# FPGA-3.net
KiCad netlist of a schematic drawn in Altium Designer
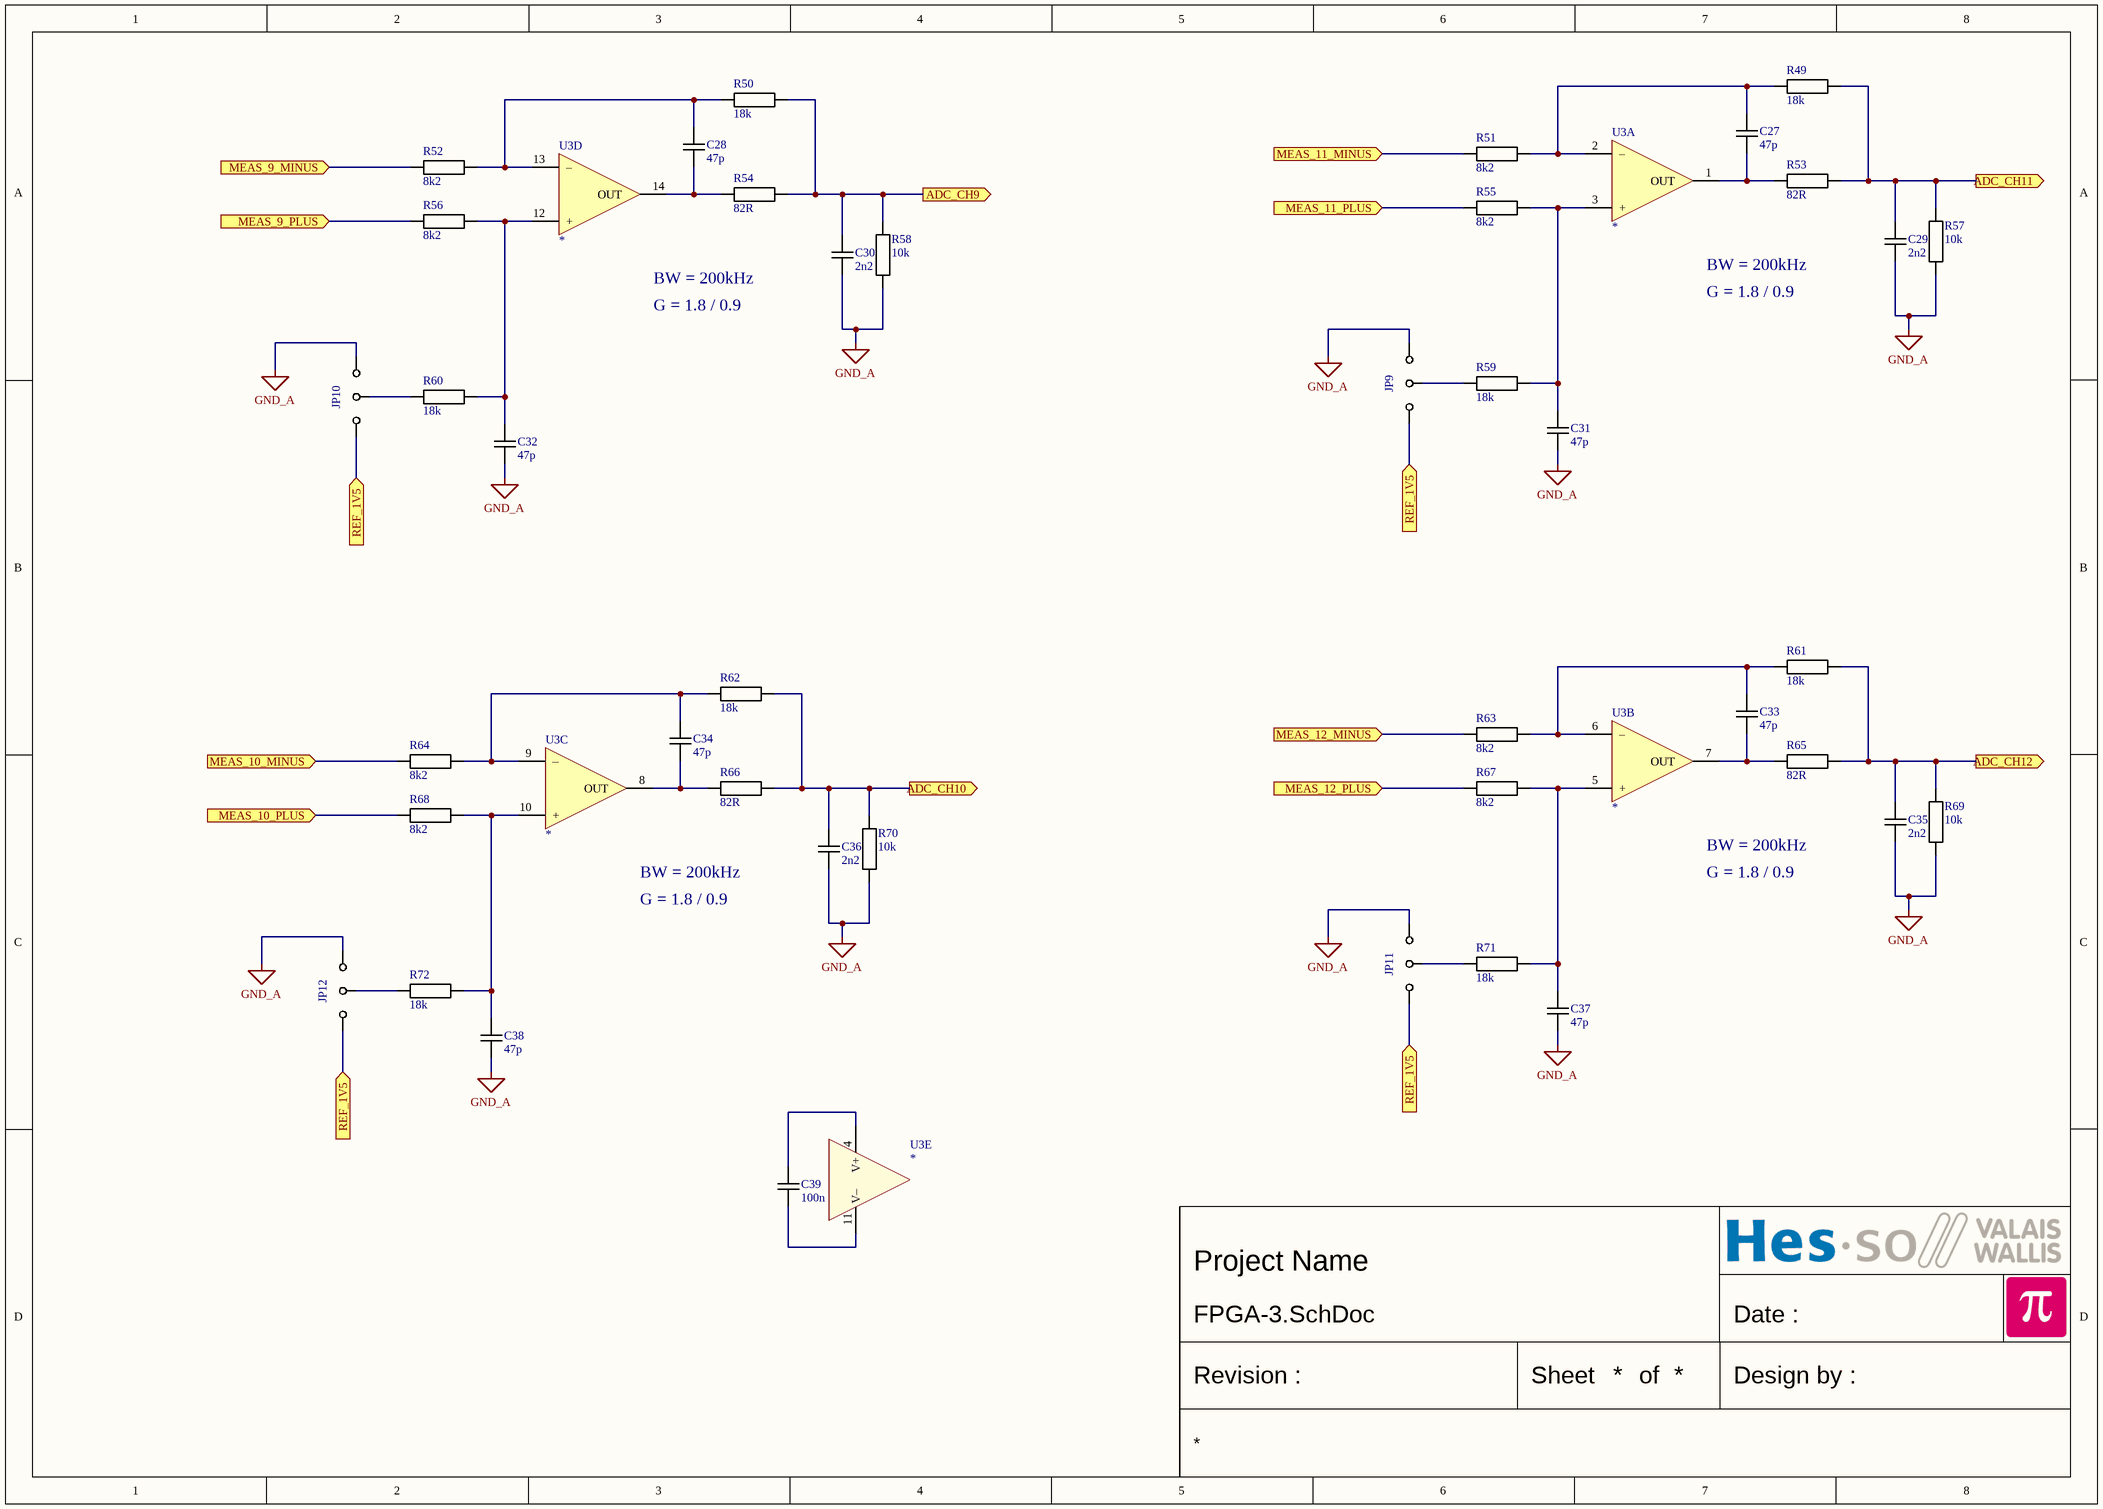
[diagram p0: FPGA-3.SchDoc]

(export (version "E")
  (design (tool "Eeschema 10.0.6"))
  (components
    (comp (ref "C27")
      (value "47p")
      (footprint "CAPACITOR 1608 REFLOW")
      (description "Capacitor X7R 10% 50V 1608(0603)")
      (libsource (lib "Capacitor") (part "Capacitor"))
    )
    (comp (ref "C28")
      (value "47p")
      (footprint "CAPACITOR 1608 REFLOW")
      (description "Capacitor X7R 10% 50V 1608(0603)")
      (libsource (lib "Capacitor") (part "Capacitor"))
    )
    (comp (ref "C29")
      (value "2n2")
      (footprint "CAPACITOR 1608 REFLOW")
      (description "Capacitor X7R 10% 50V 1608(0603)")
      (libsource (lib "Capacitor") (part "Capacitor"))
    )
    (comp (ref "C30")
      (value "2n2")
      (footprint "CAPACITOR 1608 REFLOW")
      (description "Capacitor X7R 10% 50V 1608(0603)")
      (libsource (lib "Capacitor") (part "Capacitor"))
    )
    (comp (ref "C31")
      (value "47p")
      (footprint "CAPACITOR 1608 REFLOW")
      (description "Capacitor X7R 10% 50V 1608(0603)")
      (libsource (lib "Capacitor") (part "Capacitor"))
    )
    (comp (ref "C32")
      (value "47p")
      (footprint "CAPACITOR 1608 REFLOW")
      (description "Capacitor X7R 10% 50V 1608(0603)")
      (libsource (lib "Capacitor") (part "Capacitor"))
    )
    (comp (ref "C33")
      (value "47p")
      (footprint "CAPACITOR 1608 REFLOW")
      (description "Capacitor X7R 10% 50V 1608(0603)")
      (libsource (lib "Capacitor") (part "Capacitor"))
    )
    (comp (ref "C34")
      (value "47p")
      (footprint "CAPACITOR 1608 REFLOW")
      (description "Capacitor X7R 10% 50V 1608(0603)")
      (libsource (lib "Capacitor") (part "Capacitor"))
    )
    (comp (ref "C35")
      (value "2n2")
      (footprint "CAPACITOR 1608 REFLOW")
      (description "Capacitor X7R 10% 50V 1608(0603)")
      (libsource (lib "Capacitor") (part "Capacitor"))
    )
    (comp (ref "C36")
      (value "2n2")
      (footprint "CAPACITOR 1608 REFLOW")
      (description "Capacitor X7R 10% 50V 1608(0603)")
      (libsource (lib "Capacitor") (part "Capacitor"))
    )
    (comp (ref "C37")
      (value "47p")
      (footprint "CAPACITOR 1608 REFLOW")
      (description "Capacitor X7R 10% 50V 1608(0603)")
      (libsource (lib "Capacitor") (part "Capacitor"))
    )
    (comp (ref "C38")
      (value "47p")
      (footprint "CAPACITOR 1608 REFLOW")
      (description "Capacitor X7R 10% 50V 1608(0603)")
      (libsource (lib "Capacitor") (part "Capacitor"))
    )
    (comp (ref "C39")
      (value "100n")
      (footprint "CAPACITOR 1608 REFLOW")
      (description "Capacitor X7R 10% 50V 1608(0603)")
      (libsource (lib "Capacitor") (part "Capacitor"))
    )
    (comp (ref "JP9")
      (value "{Value}")
      (footprint "JUMPER3 SMD 1608")
      (description "JUMPER 3 POS")
      (libsource (lib "Jumper") (part "JUMPER 3 POS"))
    )
    (comp (ref "JP10")
      (value "{Value}")
      (footprint "JUMPER3 SMD 1608")
      (description "JUMPER 3 POS")
      (libsource (lib "Jumper") (part "JUMPER 3 POS"))
    )
    (comp (ref "JP11")
      (value "{Value}")
      (footprint "JUMPER3 SMD 1608")
      (description "JUMPER 3 POS")
      (libsource (lib "Jumper") (part "JUMPER 3 POS"))
    )
    (comp (ref "JP12")
      (value "{Value}")
      (footprint "JUMPER3 SMD 1608")
      (description "JUMPER 3 POS")
      (libsource (lib "Jumper") (part "JUMPER 3 POS"))
    )
    (comp (ref "R49")
      (value "18k")
      (footprint "RESISTOR 1608 REFLOW")
      (description "Resistor 1% 50V 100mW 1608(0603)")
      (libsource (lib "Resistor") (part "Resistor"))
    )
    (comp (ref "R50")
      (value "18k")
      (footprint "RESISTOR 1608 REFLOW")
      (description "Resistor 1% 50V 100mW 1608(0603)")
      (libsource (lib "Resistor") (part "Resistor"))
    )
    (comp (ref "R51")
      (value "8k2")
      (footprint "RESISTOR 1608 REFLOW")
      (description "Resistor 1% 50V 100mW 1608(0603)")
      (libsource (lib "Resistor") (part "Resistor"))
    )
    (comp (ref "R52")
      (value "8k2")
      (footprint "RESISTOR 1608 REFLOW")
      (description "Resistor 1% 50V 100mW 1608(0603)")
      (libsource (lib "Resistor") (part "Resistor"))
    )
    (comp (ref "R53")
      (value "82R")
      (footprint "RESISTOR 1608 REFLOW")
      (description "Resistor 1% 50V 100mW 1608(0603)")
      (libsource (lib "Resistor") (part "Resistor"))
    )
    (comp (ref "R54")
      (value "82R")
      (footprint "RESISTOR 1608 REFLOW")
      (description "Resistor 1% 50V 100mW 1608(0603)")
      (libsource (lib "Resistor") (part "Resistor"))
    )
    (comp (ref "R55")
      (value "8k2")
      (footprint "RESISTOR 1608 REFLOW")
      (description "Resistor 1% 50V 100mW 1608(0603)")
      (libsource (lib "Resistor") (part "Resistor"))
    )
    (comp (ref "R56")
      (value "8k2")
      (footprint "RESISTOR 1608 REFLOW")
      (description "Resistor 1% 50V 100mW 1608(0603)")
      (libsource (lib "Resistor") (part "Resistor"))
    )
    (comp (ref "R57")
      (value "10k")
      (footprint "RESISTOR 1608 REFLOW")
      (description "Resistor 1% 50V 100mW 1608(0603)")
      (libsource (lib "Resistor") (part "Resistor"))
    )
    (comp (ref "R58")
      (value "10k")
      (footprint "RESISTOR 1608 REFLOW")
      (description "Resistor 1% 50V 100mW 1608(0603)")
      (libsource (lib "Resistor") (part "Resistor"))
    )
    (comp (ref "R59")
      (value "18k")
      (footprint "RESISTOR 1608 REFLOW")
      (description "Resistor 1% 50V 100mW 1608(0603)")
      (libsource (lib "Resistor") (part "Resistor"))
    )
    (comp (ref "R60")
      (value "18k")
      (footprint "RESISTOR 1608 REFLOW")
      (description "Resistor 1% 50V 100mW 1608(0603)")
      (libsource (lib "Resistor") (part "Resistor"))
    )
    (comp (ref "R61")
      (value "18k")
      (footprint "RESISTOR 1608 REFLOW")
      (description "Resistor 1% 50V 100mW 1608(0603)")
      (libsource (lib "Resistor") (part "Resistor"))
    )
    (comp (ref "R62")
      (value "18k")
      (footprint "RESISTOR 1608 REFLOW")
      (description "Resistor 1% 50V 100mW 1608(0603)")
      (libsource (lib "Resistor") (part "Resistor"))
    )
    (comp (ref "R63")
      (value "8k2")
      (footprint "RESISTOR 1608 REFLOW")
      (description "Resistor 1% 50V 100mW 1608(0603)")
      (libsource (lib "Resistor") (part "Resistor"))
    )
    (comp (ref "R64")
      (value "8k2")
      (footprint "RESISTOR 1608 REFLOW")
      (description "Resistor 1% 50V 100mW 1608(0603)")
      (libsource (lib "Resistor") (part "Resistor"))
    )
    (comp (ref "R65")
      (value "82R")
      (footprint "RESISTOR 1608 REFLOW")
      (description "Resistor 1% 50V 100mW 1608(0603)")
      (libsource (lib "Resistor") (part "Resistor"))
    )
    (comp (ref "R66")
      (value "82R")
      (footprint "RESISTOR 1608 REFLOW")
      (description "Resistor 1% 50V 100mW 1608(0603)")
      (libsource (lib "Resistor") (part "Resistor"))
    )
    (comp (ref "R67")
      (value "8k2")
      (footprint "RESISTOR 1608 REFLOW")
      (description "Resistor 1% 50V 100mW 1608(0603)")
      (libsource (lib "Resistor") (part "Resistor"))
    )
    (comp (ref "R68")
      (value "8k2")
      (footprint "RESISTOR 1608 REFLOW")
      (description "Resistor 1% 50V 100mW 1608(0603)")
      (libsource (lib "Resistor") (part "Resistor"))
    )
    (comp (ref "R69")
      (value "10k")
      (footprint "RESISTOR 1608 REFLOW")
      (description "Resistor 1% 50V 100mW 1608(0603)")
      (libsource (lib "Resistor") (part "Resistor"))
    )
    (comp (ref "R70")
      (value "10k")
      (footprint "RESISTOR 1608 REFLOW")
      (description "Resistor 1% 50V 100mW 1608(0603)")
      (libsource (lib "Resistor") (part "Resistor"))
    )
    (comp (ref "R71")
      (value "18k")
      (footprint "RESISTOR 1608 REFLOW")
      (description "Resistor 1% 50V 100mW 1608(0603)")
      (libsource (lib "Resistor") (part "Resistor"))
    )
    (comp (ref "R72")
      (value "18k")
      (footprint "RESISTOR 1608 REFLOW")
      (description "Resistor 1% 50V 100mW 1608(0603)")
      (libsource (lib "Resistor") (part "Resistor"))
    )
    (comp (ref "U3")
      (value "*")
      (footprint "SO14 P1.27 C4.0X8.8 H1.75")
      (description "Generic quad OPA 14 pins")
      (libsource (lib "Amplifier") (part "OPA QUAD"))
    )
  )
  (nets
    (net (code "1") (name "/ADC_CH9") (class "Default")
      (node (ref "C30") (pin "2") (pinfunction "2_2") (pintype "passive"))
      (node (ref "R50") (pin "2") (pinfunction "2_2") (pintype "passive"))
      (node (ref "R54") (pin "2") (pinfunction "2_2") (pintype "passive"))
      (node (ref "R58") (pin "1") (pinfunction "1_1") (pintype "passive"))
    )
    (net (code "2") (name "/ADC_CH10") (class "Default")
      (node (ref "C36") (pin "2") (pinfunction "2_2") (pintype "passive"))
      (node (ref "R62") (pin "2") (pinfunction "2_2") (pintype "passive"))
      (node (ref "R66") (pin "2") (pinfunction "2_2") (pintype "passive"))
      (node (ref "R70") (pin "1") (pinfunction "1_1") (pintype "passive"))
    )
    (net (code "3") (name "/ADC_CH11") (class "Default")
      (node (ref "C29") (pin "2") (pinfunction "2_2") (pintype "passive"))
      (node (ref "R49") (pin "2") (pinfunction "2_2") (pintype "passive"))
      (node (ref "R53") (pin "2") (pinfunction "2_2") (pintype "passive"))
      (node (ref "R57") (pin "1") (pinfunction "1_1") (pintype "passive"))
    )
    (net (code "4") (name "/ADC_CH12") (class "Default")
      (node (ref "C35") (pin "2") (pinfunction "2_2") (pintype "passive"))
      (node (ref "R61") (pin "2") (pinfunction "2_2") (pintype "passive"))
      (node (ref "R65") (pin "2") (pinfunction "2_2") (pintype "passive"))
      (node (ref "R69") (pin "1") (pinfunction "1_1") (pintype "passive"))
    )
    (net (code "5") (name "/MEAS_9_MINUS") (class "Default")
      (node (ref "R52") (pin "1") (pinfunction "1_1") (pintype "passive"))
    )
    (net (code "6") (name "/MEAS_9_PLUS") (class "Default")
      (node (ref "R56") (pin "1") (pinfunction "1_1") (pintype "passive"))
    )
    (net (code "7") (name "/MEAS_10_MINUS") (class "Default")
      (node (ref "R64") (pin "1") (pinfunction "1_1") (pintype "passive"))
    )
    (net (code "8") (name "/MEAS_10_PLUS") (class "Default")
      (node (ref "R68") (pin "1") (pinfunction "1_1") (pintype "passive"))
    )
    (net (code "9") (name "/MEAS_11_MINUS") (class "Default")
      (node (ref "R51") (pin "1") (pinfunction "1_1") (pintype "passive"))
    )
    (net (code "10") (name "/MEAS_11_PLUS") (class "Default")
      (node (ref "R55") (pin "1") (pinfunction "1_1") (pintype "passive"))
    )
    (net (code "11") (name "/MEAS_12_MINUS") (class "Default")
      (node (ref "R63") (pin "1") (pinfunction "1_1") (pintype "passive"))
    )
    (net (code "12") (name "/MEAS_12_PLUS") (class "Default")
      (node (ref "R67") (pin "1") (pinfunction "1_1") (pintype "passive"))
    )
    (net (code "13") (name "/REF_1V5") (class "Default")
      (node (ref "JP10") (pin "1") (pinfunction "1_1") (pintype "passive"))
      (node (ref "JP11") (pin "1") (pinfunction "1_1") (pintype "passive"))
      (node (ref "JP12") (pin "1") (pinfunction "1_1") (pintype "passive"))
      (node (ref "JP9") (pin "1") (pinfunction "1_1") (pintype "passive"))
    )
    (net (code "14") (name "GND_A") (class "Default")
      (node (ref "C29") (pin "1") (pinfunction "1_1") (pintype "passive"))
      (node (ref "C30") (pin "1") (pinfunction "1_1") (pintype "passive"))
      (node (ref "C31") (pin "1") (pinfunction "1_1") (pintype "passive"))
      (node (ref "C32") (pin "1") (pinfunction "1_1") (pintype "passive"))
      (node (ref "C35") (pin "1") (pinfunction "1_1") (pintype "passive"))
      (node (ref "C36") (pin "1") (pinfunction "1_1") (pintype "passive"))
      (node (ref "C37") (pin "1") (pinfunction "1_1") (pintype "passive"))
      (node (ref "C38") (pin "1") (pinfunction "1_1") (pintype "passive"))
      (node (ref "JP10") (pin "3") (pinfunction "3_3") (pintype "passive"))
      (node (ref "JP11") (pin "3") (pinfunction "3_3") (pintype "passive"))
      (node (ref "JP12") (pin "3") (pinfunction "3_3") (pintype "passive"))
      (node (ref "JP9") (pin "3") (pinfunction "3_3") (pintype "passive"))
      (node (ref "R57") (pin "2") (pinfunction "2_2") (pintype "passive"))
      (node (ref "R58") (pin "2") (pinfunction "2_2") (pintype "passive"))
      (node (ref "R69") (pin "2") (pinfunction "2_2") (pintype "passive"))
      (node (ref "R70") (pin "2") (pinfunction "2_2") (pintype "passive"))
    )
    (net (code "15") (name "Net-(JP9-Pad2)") (class "Default")
      (node (ref "JP9") (pin "2") (pinfunction "2_2") (pintype "passive"))
      (node (ref "R59") (pin "2") (pinfunction "2_2") (pintype "passive"))
    )
    (net (code "16") (name "Net-(JP10-Pad2)") (class "Default")
      (node (ref "JP10") (pin "2") (pinfunction "2_2") (pintype "passive"))
      (node (ref "R60") (pin "2") (pinfunction "2_2") (pintype "passive"))
    )
    (net (code "17") (name "Net-(JP11-Pad2)") (class "Default")
      (node (ref "JP11") (pin "2") (pinfunction "2_2") (pintype "passive"))
      (node (ref "R71") (pin "2") (pinfunction "2_2") (pintype "passive"))
    )
    (net (code "18") (name "Net-(JP12-Pad2)") (class "Default")
      (node (ref "JP12") (pin "2") (pinfunction "2_2") (pintype "passive"))
      (node (ref "R72") (pin "2") (pinfunction "2_2") (pintype "passive"))
    )
    (net (code "19") (name "Net-(U3A-+)") (class "Default")
      (node (ref "C31") (pin "2") (pinfunction "2_2") (pintype "passive"))
      (node (ref "R55") (pin "2") (pinfunction "2_2") (pintype "passive"))
      (node (ref "R59") (pin "1") (pinfunction "1_1") (pintype "passive"))
      (node (ref "U3") (pin "3") (pinfunction "+_3") (pintype "passive"))
    )
    (net (code "20") (name "Net-(U3A-OUT)") (class "Default")
      (node (ref "C27") (pin "1") (pinfunction "1_1") (pintype "passive"))
      (node (ref "R53") (pin "1") (pinfunction "1_1") (pintype "passive"))
      (node (ref "U3") (pin "1") (pinfunction "OUT_1") (pintype "passive"))
    )
    (net (code "21") (name "Net-(U3A-–)") (class "Default")
      (node (ref "C27") (pin "2") (pinfunction "2_2") (pintype "passive"))
      (node (ref "R49") (pin "1") (pinfunction "1_1") (pintype "passive"))
      (node (ref "R51") (pin "2") (pinfunction "2_2") (pintype "passive"))
      (node (ref "U3") (pin "2") (pinfunction "–_2") (pintype "passive"))
    )
    (net (code "22") (name "Net-(U3B-+)") (class "Default")
      (node (ref "C37") (pin "2") (pinfunction "2_2") (pintype "passive"))
      (node (ref "R67") (pin "2") (pinfunction "2_2") (pintype "passive"))
      (node (ref "R71") (pin "1") (pinfunction "1_1") (pintype "passive"))
      (node (ref "U3") (pin "5") (pinfunction "+_5") (pintype "passive"))
    )
    (net (code "23") (name "Net-(U3B-OUT)") (class "Default")
      (node (ref "C33") (pin "1") (pinfunction "1_1") (pintype "passive"))
      (node (ref "R65") (pin "1") (pinfunction "1_1") (pintype "passive"))
      (node (ref "U3") (pin "7") (pinfunction "OUT_7") (pintype "passive"))
    )
    (net (code "24") (name "Net-(U3B-–)") (class "Default")
      (node (ref "C33") (pin "2") (pinfunction "2_2") (pintype "passive"))
      (node (ref "R61") (pin "1") (pinfunction "1_1") (pintype "passive"))
      (node (ref "R63") (pin "2") (pinfunction "2_2") (pintype "passive"))
      (node (ref "U3") (pin "6") (pinfunction "–_6") (pintype "passive"))
    )
    (net (code "25") (name "Net-(U3C-+)") (class "Default")
      (node (ref "C38") (pin "2") (pinfunction "2_2") (pintype "passive"))
      (node (ref "R68") (pin "2") (pinfunction "2_2") (pintype "passive"))
      (node (ref "R72") (pin "1") (pinfunction "1_1") (pintype "passive"))
      (node (ref "U3") (pin "10") (pinfunction "+_10") (pintype "passive"))
    )
    (net (code "26") (name "Net-(U3C-OUT)") (class "Default")
      (node (ref "C34") (pin "1") (pinfunction "1_1") (pintype "passive"))
      (node (ref "R66") (pin "1") (pinfunction "1_1") (pintype "passive"))
      (node (ref "U3") (pin "8") (pinfunction "OUT_8") (pintype "passive"))
    )
    (net (code "27") (name "Net-(U3C-–)") (class "Default")
      (node (ref "C34") (pin "2") (pinfunction "2_2") (pintype "passive"))
      (node (ref "R62") (pin "1") (pinfunction "1_1") (pintype "passive"))
      (node (ref "R64") (pin "2") (pinfunction "2_2") (pintype "passive"))
      (node (ref "U3") (pin "9") (pinfunction "–_9") (pintype "passive"))
    )
    (net (code "28") (name "Net-(U3D-+)") (class "Default")
      (node (ref "C32") (pin "2") (pinfunction "2_2") (pintype "passive"))
      (node (ref "R56") (pin "2") (pinfunction "2_2") (pintype "passive"))
      (node (ref "R60") (pin "1") (pinfunction "1_1") (pintype "passive"))
      (node (ref "U3") (pin "12") (pinfunction "+_12") (pintype "passive"))
    )
    (net (code "29") (name "Net-(U3D-OUT)") (class "Default")
      (node (ref "C28") (pin "1") (pinfunction "1_1") (pintype "passive"))
      (node (ref "R54") (pin "1") (pinfunction "1_1") (pintype "passive"))
      (node (ref "U3") (pin "14") (pinfunction "OUT_14") (pintype "passive"))
    )
    (net (code "30") (name "Net-(U3D-–)") (class "Default")
      (node (ref "C28") (pin "2") (pinfunction "2_2") (pintype "passive"))
      (node (ref "R50") (pin "1") (pinfunction "1_1") (pintype "passive"))
      (node (ref "R52") (pin "2") (pinfunction "2_2") (pintype "passive"))
      (node (ref "U3") (pin "13") (pinfunction "–_13") (pintype "passive"))
    )
    (net (code "31") (name "Net-(U3E-V+)") (class "Default")
      (node (ref "C39") (pin "2") (pinfunction "2_2") (pintype "passive"))
      (node (ref "U3") (pin "4") (pinfunction "V+_4") (pintype "passive"))
    )
    (net (code "32") (name "Net-(U3E-V–)") (class "Default")
      (node (ref "C39") (pin "1") (pinfunction "1_1") (pintype "passive"))
      (node (ref "U3") (pin "11") (pinfunction "V–_11") (pintype "passive"))
    )
  )
)
